# devboard-rf.net
KiCad netlist of a schematic drawn in EAGLE
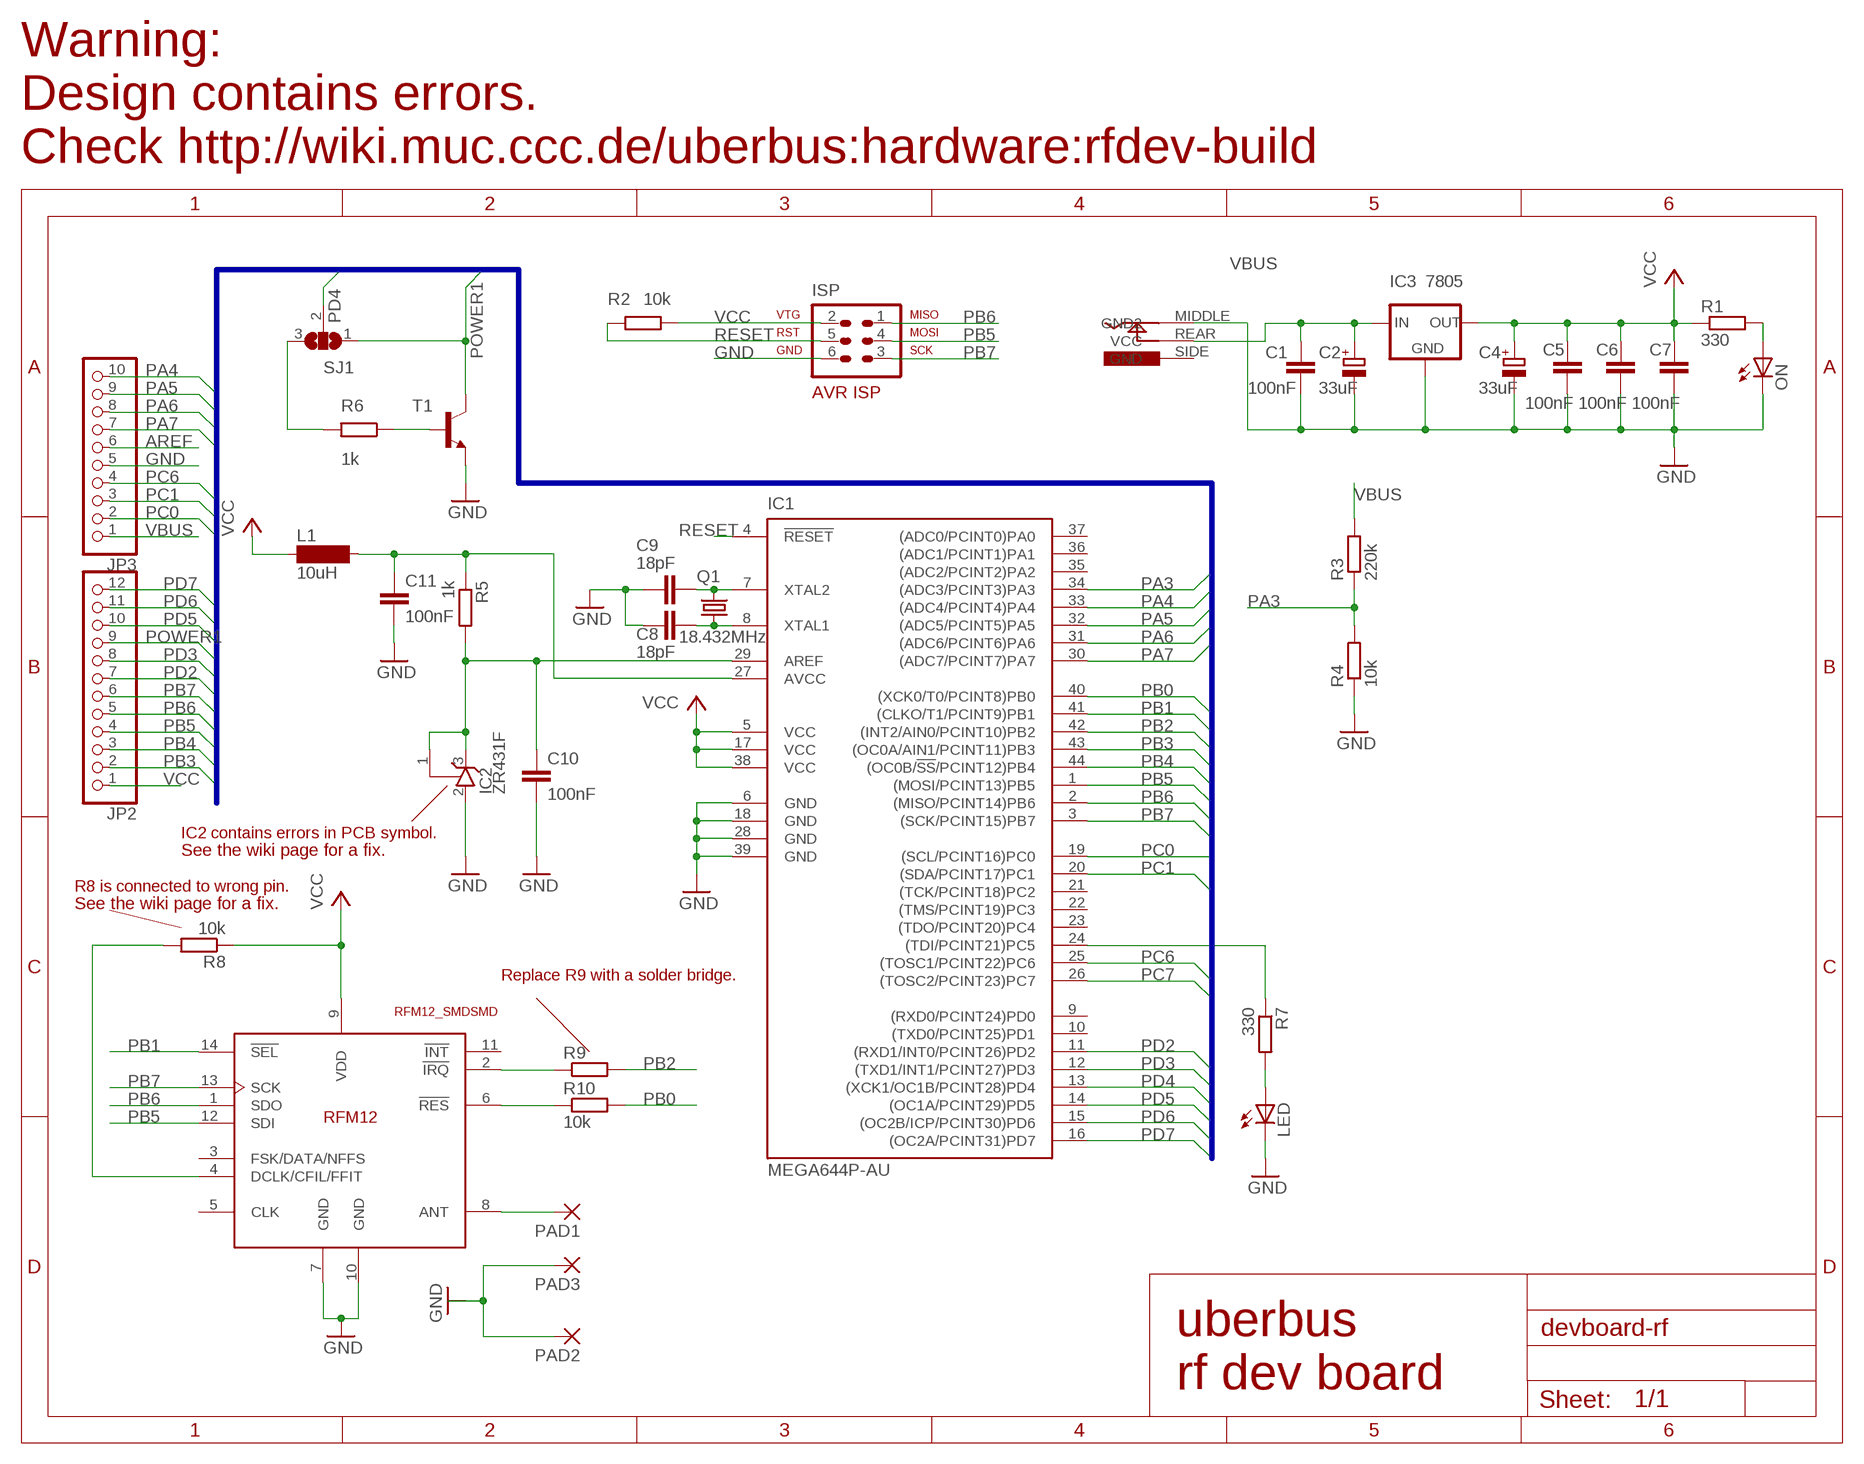
[diagram p0: schematic, sheet 1]

(export (version "E")
  (design (tool "Eeschema 10.0.6"))
  (components
    (comp (ref "C1")
      (value "100nF")
      (footprint "eagle-import:C0805K")
      (libsource (lib "eagle-import") (part "C-EUC0805K"))
    )
    (comp (ref "C2")
      (value "33uF")
      (footprint "eagle-import:E2,5-5")
      (libsource (lib "eagle-import") (part "CPOL-EUE2.5-5"))
    )
    (comp (ref "C4")
      (value "33uF")
      (footprint "eagle-import:E2,5-5")
      (libsource (lib "eagle-import") (part "CPOL-EUE2.5-5"))
    )
    (comp (ref "C5")
      (value "100nF")
      (footprint "eagle-import:C0805K")
      (libsource (lib "eagle-import") (part "C-EUC0805K"))
    )
    (comp (ref "C6")
      (value "100nF")
      (footprint "eagle-import:C0805K")
      (libsource (lib "eagle-import") (part "C-EUC0805K"))
    )
    (comp (ref "C7")
      (value "100nF")
      (footprint "eagle-import:C0805K")
      (libsource (lib "eagle-import") (part "C-EUC0805K"))
    )
    (comp (ref "C8")
      (value "18pF")
      (footprint "eagle-import:C0805K")
      (libsource (lib "eagle-import") (part "C-EUC0805K"))
    )
    (comp (ref "C9")
      (value "18pF")
      (footprint "eagle-import:C0805K")
      (libsource (lib "eagle-import") (part "C-EUC0805K"))
    )
    (comp (ref "C10")
      (value "100nF")
      (footprint "eagle-import:C0805K")
      (libsource (lib "eagle-import") (part "C-EUC0805K"))
    )
    (comp (ref "C11")
      (value "100nF")
      (footprint "eagle-import:C0805K")
      (libsource (lib "eagle-import") (part "C-EUC0805K"))
    )
    (comp (ref "IC1")
      (value "MEGA644P-AU")
      (footprint "eagle-import:TQFP44")
      (libsource (lib "eagle-import") (part "MEGA164P/324P/644P-AU"))
    )
    (comp (ref "IC2")
      (value "ZR431F")
      (footprint "eagle-import:SOT32")
      (libsource (lib "eagle-import") (part "ZR431F"))
    )
    (comp (ref "IC3")
      (value "7805")
      (footprint "eagle-import:78XXS")
      (libsource (lib "eagle-import") (part "78XXS"))
    )
    (comp (ref "ISP")
      (value "AVR-ISP-6")
      (footprint "eagle-import:AVR-ISP-6")
      (libsource (lib "eagle-import") (part "AVR-ISP-6"))
    )
    (comp (ref "JP2")
      (value "PINHD-1X12")
      (footprint "eagle-import:1X12")
      (libsource (lib "eagle-import") (part "PINHD-1X12"))
    )
    (comp (ref "JP3")
      (value "PINHD-1X10")
      (footprint "eagle-import:1X10")
      (libsource (lib "eagle-import") (part "PINHD-1X10"))
    )
    (comp (ref "L1")
      (value "10uH")
      (footprint "eagle-import:SM-1206")
      (libsource (lib "eagle-import") (part "SM-1206"))
    )
    (comp (ref "LED")
      (value "LEDCHIPLED_0805")
      (footprint "eagle-import:CHIPLED_0805")
      (libsource (lib "eagle-import") (part "LEDCHIPLED_0805"))
    )
    (comp (ref "ON")
      (value "LEDCHIPLED_0805")
      (footprint "eagle-import:CHIPLED_0805")
      (libsource (lib "eagle-import") (part "LEDCHIPLED_0805"))
    )
    (comp (ref "PAD1")
      (value "SMD2")
      (footprint "eagle-import:SMD1,27-2,54")
      (libsource (lib "eagle-import") (part "SMD2"))
    )
    (comp (ref "PAD2")
      (value "SMD2")
      (footprint "eagle-import:SMD1,27-2,54")
      (libsource (lib "eagle-import") (part "SMD2"))
    )
    (comp (ref "PAD3")
      (value "SMD2")
      (footprint "eagle-import:SMD1,27-2,54")
      (libsource (lib "eagle-import") (part "SMD2"))
    )
    (comp (ref "Q1")
      (value "18.432MHz")
      (footprint "eagle-import:HC49UP")
      (libsource (lib "eagle-import") (part "CRYSTALHC49UP"))
    )
    (comp (ref "R1")
      (value "330")
      (footprint "eagle-import:R0805")
      (libsource (lib "eagle-import") (part "R-EU_R0805"))
    )
    (comp (ref "R2")
      (value "10k")
      (footprint "eagle-import:R0805")
      (libsource (lib "eagle-import") (part "R-EU_R0805"))
    )
    (comp (ref "R3")
      (value "220k")
      (footprint "eagle-import:R0805")
      (libsource (lib "eagle-import") (part "R-EU_R0805"))
    )
    (comp (ref "R4")
      (value "10k")
      (footprint "eagle-import:R0805")
      (libsource (lib "eagle-import") (part "R-EU_R0805"))
    )
    (comp (ref "R5")
      (value "1k")
      (footprint "eagle-import:R0805")
      (libsource (lib "eagle-import") (part "R-EU_R0805"))
    )
    (comp (ref "R6")
      (value "1k")
      (footprint "eagle-import:R0805")
      (libsource (lib "eagle-import") (part "R-EU_R0805"))
    )
    (comp (ref "R7")
      (value "330")
      (footprint "eagle-import:R0805")
      (libsource (lib "eagle-import") (part "R-EU_R0805"))
    )
    (comp (ref "R8")
      (value "10k")
      (footprint "eagle-import:R0805")
      (libsource (lib "eagle-import") (part "R-EU_R0805"))
    )
    (comp (ref "R9")
      (value "0")
      (footprint "eagle-import:R0805")
      (libsource (lib "eagle-import") (part "R-EU_R0805"))
    )
    (comp (ref "R10")
      (value "10k")
      (footprint "eagle-import:R0805")
      (libsource (lib "eagle-import") (part "R-EU_R0805"))
    )
    (comp (ref "SJ1")
      (value "SJ2W")
      (footprint "eagle-import:SJ_2")
      (libsource (lib "eagle-import") (part "SJ2W"))
    )
    (comp (ref "T1")
      (value "MMBT2222ALT1-NPN-SOT23-BEC")
      (footprint "eagle-import:SOT23-BEC")
      (libsource (lib "eagle-import") (part "-NPN-SOT23-BECMMBT2222ALT1"))
    )
    (comp (ref "U$1")
      (value "RFM12_SMDSMD")
      (footprint "eagle-import:RFM12")
      (libsource (lib "eagle-import") (part "RFM12_SMDSMD"))
    )
    (comp (ref "U$2")
      (value "JACK-2.1MM")
      (footprint "eagle-import:JACK-2.1MM")
      (libsource (lib "eagle-import") (part "JACK-2.1MM"))
    )
  )
  (nets
    (net (code "1") (name "/AREF") (class "Default")
      (node (ref "C10") (pin "1") (pinfunction "1_1") (pintype "passive"))
      (node (ref "IC1") (pin "29") (pinfunction "AREF_29") (pintype "power_in"))
      (node (ref "IC2") (pin "1") (pinfunction "R_1") (pintype "passive"))
      (node (ref "IC2") (pin "3") (pinfunction "C_3") (pintype "passive"))
      (node (ref "JP3") (pin "6") (pinfunction "6_6") (pintype "passive"))
      (node (ref "R5") (pin "2") (pinfunction "2_2") (pintype "passive"))
    )
    (net (code "2") (name "/PA3") (class "Default")
      (node (ref "IC1") (pin "34") (pinfunction "(ADC3/PCINT3)PA3_34") (pintype "bidirectional"))
      (node (ref "R3") (pin "1") (pinfunction "1_1") (pintype "passive"))
      (node (ref "R4") (pin "2") (pinfunction "2_2") (pintype "passive"))
    )
    (net (code "3") (name "/PA4") (class "Default")
      (node (ref "IC1") (pin "33") (pinfunction "(ADC4/PCINT4)PA4_33") (pintype "bidirectional"))
      (node (ref "JP3") (pin "10") (pinfunction "10_10") (pintype "passive"))
    )
    (net (code "4") (name "/PA5") (class "Default")
      (node (ref "IC1") (pin "32") (pinfunction "(ADC5/PCINT5)PA5_32") (pintype "bidirectional"))
      (node (ref "JP3") (pin "9") (pinfunction "9_9") (pintype "passive"))
    )
    (net (code "5") (name "/PA6") (class "Default")
      (node (ref "IC1") (pin "31") (pinfunction "(ADC6/PCINT6)PA6_31") (pintype "bidirectional"))
      (node (ref "JP3") (pin "8") (pinfunction "8_8") (pintype "passive"))
    )
    (net (code "6") (name "/PA7") (class "Default")
      (node (ref "IC1") (pin "30") (pinfunction "(ADC7/PCINT7)PA7_30") (pintype "bidirectional"))
      (node (ref "JP3") (pin "7") (pinfunction "7_7") (pintype "passive"))
    )
    (net (code "7") (name "/PB0") (class "Default")
      (node (ref "IC1") (pin "40") (pinfunction "(XCK0/T0/PCINT8)PB0_40") (pintype "bidirectional"))
      (node (ref "R10") (pin "2") (pinfunction "2_2") (pintype "passive"))
    )
    (net (code "8") (name "/PB1") (class "Default")
      (node (ref "IC1") (pin "41") (pinfunction "(CLKO/T1/PCINT9)PB1_41") (pintype "bidirectional"))
      (node (ref "U$1") (pin "14") (pinfunction "~{SEL}_14") (pintype "input"))
    )
    (net (code "9") (name "/PB2") (class "Default")
      (node (ref "IC1") (pin "42") (pinfunction "(INT2/AIN0/PCINT10)PB2_42") (pintype "bidirectional"))
      (node (ref "R9") (pin "2") (pinfunction "2_2") (pintype "passive"))
    )
    (net (code "10") (name "/PB3") (class "Default")
      (node (ref "IC1") (pin "43") (pinfunction "(OC0A/AIN1/PCINT11)PB3_43") (pintype "bidirectional"))
      (node (ref "JP2") (pin "2") (pinfunction "2_2") (pintype "passive"))
    )
    (net (code "11") (name "/PB4") (class "Default")
      (node (ref "IC1") (pin "44") (pinfunction "(OC0B/~{SS}/PCINT12)PB4_44") (pintype "bidirectional"))
      (node (ref "JP2") (pin "3") (pinfunction "3_3") (pintype "passive"))
    )
    (net (code "12") (name "/PB5") (class "Default")
      (node (ref "IC1") (pin "1") (pinfunction "(MOSI/PCINT13)PB5_1") (pintype "bidirectional"))
      (node (ref "ISP") (pin "4") (pinfunction "4_4") (pintype "passive"))
      (node (ref "JP2") (pin "4") (pinfunction "4_4") (pintype "passive"))
      (node (ref "U$1") (pin "12") (pinfunction "SDI_12") (pintype "input"))
    )
    (net (code "13") (name "/PB6") (class "Default")
      (node (ref "IC1") (pin "2") (pinfunction "(MISO/PCINT14)PB6_2") (pintype "bidirectional"))
      (node (ref "ISP") (pin "1") (pinfunction "1_1") (pintype "passive"))
      (node (ref "JP2") (pin "5") (pinfunction "5_5") (pintype "passive"))
      (node (ref "U$1") (pin "1") (pinfunction "SDO_1") (pintype "output"))
    )
    (net (code "14") (name "/PB7") (class "Default")
      (node (ref "IC1") (pin "3") (pinfunction "(SCK/PCINT15)PB7_3") (pintype "bidirectional"))
      (node (ref "ISP") (pin "3") (pinfunction "3_3") (pintype "passive"))
      (node (ref "JP2") (pin "6") (pinfunction "6_6") (pintype "passive"))
      (node (ref "U$1") (pin "13") (pinfunction "SCK_13") (pintype "input"))
    )
    (net (code "15") (name "/PC0") (class "Default")
      (node (ref "IC1") (pin "19") (pinfunction "(SCL/PCINT16)PC0_19") (pintype "bidirectional"))
      (node (ref "JP3") (pin "2") (pinfunction "2_2") (pintype "passive"))
    )
    (net (code "16") (name "/PC1") (class "Default")
      (node (ref "IC1") (pin "20") (pinfunction "(SDA/PCINT17)PC1_20") (pintype "bidirectional"))
      (node (ref "JP3") (pin "3") (pinfunction "3_3") (pintype "passive"))
    )
    (net (code "17") (name "/PC6") (class "Default")
      (node (ref "IC1") (pin "25") (pinfunction "(TOSC1/PCINT22)PC6_25") (pintype "bidirectional"))
      (node (ref "JP3") (pin "4") (pinfunction "4_4") (pintype "passive"))
    )
    (net (code "18") (name "/PC7") (class "Default")
      (node (ref "IC1") (pin "26") (pinfunction "(TOSC2/PCINT23)PC7_26") (pintype "bidirectional"))
    )
    (net (code "19") (name "/PD2") (class "Default")
      (node (ref "IC1") (pin "11") (pinfunction "(RXD1/INT0/PCINT26)PD2_11") (pintype "bidirectional"))
      (node (ref "JP2") (pin "7") (pinfunction "7_7") (pintype "passive"))
    )
    (net (code "20") (name "/PD3") (class "Default")
      (node (ref "IC1") (pin "12") (pinfunction "(TXD1/INT1/PCINT27)PD3_12") (pintype "bidirectional"))
      (node (ref "JP2") (pin "8") (pinfunction "8_8") (pintype "passive"))
    )
    (net (code "21") (name "/PD4") (class "Default")
      (node (ref "IC1") (pin "13") (pinfunction "(XCK1/OC1B/PCINT28)PD4_13") (pintype "bidirectional"))
      (node (ref "SJ1") (pin "2") (pinfunction "2_2") (pintype "passive"))
    )
    (net (code "22") (name "/PD5") (class "Default")
      (node (ref "IC1") (pin "14") (pinfunction "(OC1A/PCINT29)PD5_14") (pintype "bidirectional"))
      (node (ref "JP2") (pin "10") (pinfunction "10_10") (pintype "passive"))
    )
    (net (code "23") (name "/PD6") (class "Default")
      (node (ref "IC1") (pin "15") (pinfunction "(OC2B/ICP/PCINT30)PD6_15") (pintype "bidirectional"))
      (node (ref "JP2") (pin "11") (pinfunction "11_11") (pintype "passive"))
    )
    (net (code "24") (name "/PD7") (class "Default")
      (node (ref "IC1") (pin "16") (pinfunction "(OC2A/PCINT31)PD7_16") (pintype "bidirectional"))
      (node (ref "JP2") (pin "12") (pinfunction "12_12") (pintype "passive"))
    )
    (net (code "25") (name "/POWER1") (class "Default")
      (node (ref "JP2") (pin "9") (pinfunction "9_9") (pintype "passive"))
      (node (ref "SJ1") (pin "1") (pinfunction "1_1") (pintype "passive"))
      (node (ref "T1") (pin "C") (pinfunction "C_C") (pintype "passive"))
    )
    (net (code "26") (name "/RESET") (class "Default")
      (node (ref "IC1") (pin "4") (pinfunction "~{RESET}_4") (pintype "input"))
      (node (ref "ISP") (pin "5") (pinfunction "5_5") (pintype "passive"))
      (node (ref "R2") (pin "1") (pinfunction "1_1") (pintype "passive"))
    )
    (net (code "27") (name "/VBUS") (class "Default")
      (node (ref "C1") (pin "2") (pinfunction "2_2") (pintype "passive"))
      (node (ref "C2") (pin "+") (pinfunction "+_+") (pintype "passive"))
      (node (ref "IC3") (pin "IN") (pinfunction "IN_IN") (pintype "input"))
      (node (ref "JP3") (pin "1") (pinfunction "1_1") (pintype "passive"))
      (node (ref "R3") (pin "2") (pinfunction "2_2") (pintype "passive"))
      (node (ref "U$2") (pin "REAR") (pinfunction "VCC_REAR") (pintype "bidirectional"))
    )
    (net (code "28") (name "GND") (class "Default")
      (node (ref "C1") (pin "1") (pinfunction "1_1") (pintype "passive"))
      (node (ref "C10") (pin "2") (pinfunction "2_2") (pintype "passive"))
      (node (ref "C11") (pin "2") (pinfunction "2_2") (pintype "passive"))
      (node (ref "C2") (pin "-") (pinfunction "-_-") (pintype "passive"))
      (node (ref "C4") (pin "-") (pinfunction "-_-") (pintype "passive"))
      (node (ref "C5") (pin "1") (pinfunction "1_1") (pintype "passive"))
      (node (ref "C6") (pin "1") (pinfunction "1_1") (pintype "passive"))
      (node (ref "C7") (pin "1") (pinfunction "1_1") (pintype "passive"))
      (node (ref "C8") (pin "2") (pinfunction "2_2") (pintype "passive"))
      (node (ref "C9") (pin "2") (pinfunction "2_2") (pintype "passive"))
      (node (ref "IC1") (pin "18") (pinfunction "GND_18") (pintype "power_in"))
      (node (ref "IC1") (pin "28") (pinfunction "GND_28") (pintype "power_in"))
      (node (ref "IC1") (pin "39") (pinfunction "GND_39") (pintype "power_in"))
      (node (ref "IC1") (pin "6") (pinfunction "GND_6") (pintype "power_in"))
      (node (ref "IC2") (pin "2") (pinfunction "A_2") (pintype "passive"))
      (node (ref "IC3") (pin "GND") (pinfunction "GND_GND") (pintype "input"))
      (node (ref "ISP") (pin "6") (pinfunction "6_6") (pintype "passive"))
      (node (ref "JP3") (pin "5") (pinfunction "5_5") (pintype "passive"))
      (node (ref "LED") (pin "C") (pinfunction "C_C") (pintype "passive"))
      (node (ref "ON") (pin "C") (pinfunction "C_C") (pintype "passive"))
      (node (ref "R4") (pin "1") (pinfunction "1_1") (pintype "passive"))
      (node (ref "T1") (pin "E") (pinfunction "E_E") (pintype "passive"))
      (node (ref "U$1") (pin "10") (pinfunction "GND_10") (pintype "passive"))
      (node (ref "U$1") (pin "7") (pinfunction "GND_7") (pintype "passive"))
      (node (ref "U$2") (pin "MIDDLE") (pinfunction "GND2_MIDDLE") (pintype "bidirectional"))
    )
    (net (code "29") (name "Net-(IC1-(TDI{slash}PCINT21)PC5)") (class "Default")
      (node (ref "IC1") (pin "24") (pinfunction "(TDI/PCINT21)PC5_24") (pintype "bidirectional"))
      (node (ref "R7") (pin "1") (pinfunction "1_1") (pintype "passive"))
    )
    (net (code "30") (name "Net-(IC1-AVCC)") (class "Default")
      (node (ref "C11") (pin "1") (pinfunction "1_1") (pintype "passive"))
      (node (ref "IC1") (pin "27") (pinfunction "AVCC_27") (pintype "power_in"))
      (node (ref "L1") (pin "2") (pinfunction "2_2") (pintype "passive"))
      (node (ref "R5") (pin "1") (pinfunction "1_1") (pintype "passive"))
    )
    (net (code "31") (name "Net-(IC1-XTAL1)") (class "Default")
      (node (ref "C8") (pin "1") (pinfunction "1_1") (pintype "passive"))
      (node (ref "IC1") (pin "8") (pinfunction "XTAL1_8") (pintype "input"))
      (node (ref "Q1") (pin "1") (pinfunction "1_1") (pintype "passive"))
    )
    (net (code "32") (name "Net-(IC1-XTAL2)") (class "Default")
      (node (ref "C9") (pin "1") (pinfunction "1_1") (pintype "passive"))
      (node (ref "IC1") (pin "7") (pinfunction "XTAL2_7") (pintype "output"))
      (node (ref "Q1") (pin "2") (pinfunction "2_2") (pintype "passive"))
    )
    (net (code "33") (name "Net-(LED-PadA)") (class "Default")
      (node (ref "LED") (pin "A") (pinfunction "A_A") (pintype "passive"))
      (node (ref "R7") (pin "2") (pinfunction "2_2") (pintype "passive"))
    )
    (net (code "34") (name "Net-(ON-PadA)") (class "Default")
      (node (ref "ON") (pin "A") (pinfunction "A_A") (pintype "passive"))
      (node (ref "R1") (pin "2") (pinfunction "2_2") (pintype "passive"))
    )
    (net (code "35") (name "Net-(PAD1-P)") (class "Default")
      (node (ref "PAD1") (pin "1") (pinfunction "P_1") (pintype "passive"))
      (node (ref "U$1") (pin "8") (pinfunction "ANT_8") (pintype "bidirectional"))
    )
    (net (code "36") (name "Net-(PAD2-P)") (class "Default")
      (node (ref "PAD2") (pin "1") (pinfunction "P_1") (pintype "passive"))
      (node (ref "PAD3") (pin "1") (pinfunction "P_1") (pintype "passive"))
    )
    (net (code "37") (name "Net-(R6-Pad1)") (class "Default")
      (node (ref "R6") (pin "1") (pinfunction "1_1") (pintype "passive"))
      (node (ref "T1") (pin "B") (pinfunction "B_B") (pintype "passive"))
    )
    (net (code "38") (name "Net-(R6-Pad2)") (class "Default")
      (node (ref "R6") (pin "2") (pinfunction "2_2") (pintype "passive"))
      (node (ref "SJ1") (pin "3") (pinfunction "3_3") (pintype "passive"))
    )
    (net (code "39") (name "Net-(U$1-DCLK{slash}CFIL{slash}FFIT)") (class "Default")
      (node (ref "R8") (pin "2") (pinfunction "2_2") (pintype "passive"))
      (node (ref "U$1") (pin "4") (pinfunction "DCLK/CFIL/FFIT_4") (pintype "bidirectional"))
    )
    (net (code "40") (name "Net-(U$1-~{IRQ})") (class "Default")
      (node (ref "R9") (pin "1") (pinfunction "1_1") (pintype "passive"))
      (node (ref "U$1") (pin "2") (pinfunction "~{IRQ}_2") (pintype "output"))
    )
    (net (code "41") (name "Net-(U$1-~{RES})") (class "Default")
      (node (ref "R10") (pin "1") (pinfunction "1_1") (pintype "passive"))
      (node (ref "U$1") (pin "6") (pinfunction "~{RES}_6") (pintype "bidirectional"))
    )
    (net (code "42") (name "VCC") (class "Default")
      (node (ref "C4") (pin "+") (pinfunction "+_+") (pintype "passive"))
      (node (ref "C5") (pin "2") (pinfunction "2_2") (pintype "passive"))
      (node (ref "C6") (pin "2") (pinfunction "2_2") (pintype "passive"))
      (node (ref "C7") (pin "2") (pinfunction "2_2") (pintype "passive"))
      (node (ref "IC1") (pin "17") (pinfunction "VCC_17") (pintype "power_in"))
      (node (ref "IC1") (pin "38") (pinfunction "VCC_38") (pintype "power_in"))
      (node (ref "IC1") (pin "5") (pinfunction "VCC_5") (pintype "power_in"))
      (node (ref "IC3") (pin "OUT") (pinfunction "OUT_OUT") (pintype "passive"))
      (node (ref "ISP") (pin "2") (pinfunction "2_2") (pintype "passive"))
      (node (ref "JP2") (pin "1") (pinfunction "1_1") (pintype "passive"))
      (node (ref "L1") (pin "1") (pinfunction "1_1") (pintype "passive"))
      (node (ref "R1") (pin "1") (pinfunction "1_1") (pintype "passive"))
      (node (ref "R2") (pin "2") (pinfunction "2_2") (pintype "passive"))
      (node (ref "R8") (pin "1") (pinfunction "1_1") (pintype "passive"))
      (node (ref "U$1") (pin "9") (pinfunction "VDD_9") (pintype "power_in"))
    )
    (net (code "43") (name "unconnected-(IC1-(ADC0{slash}PCINT0)PA0-Pad37)") (class "Default")
      (node (ref "IC1") (pin "37") (pinfunction "(ADC0/PCINT0)PA0_37") (pintype "bidirectional"))
    )
    (net (code "44") (name "unconnected-(IC1-(ADC1{slash}PCINT1)PA1-Pad36)") (class "Default")
      (node (ref "IC1") (pin "36") (pinfunction "(ADC1/PCINT1)PA1_36") (pintype "bidirectional"))
    )
    (net (code "45") (name "unconnected-(IC1-(ADC2{slash}PCINT2)PA2-Pad35)") (class "Default")
      (node (ref "IC1") (pin "35") (pinfunction "(ADC2/PCINT2)PA2_35") (pintype "bidirectional"))
    )
    (net (code "46") (name "unconnected-(IC1-(RXD0{slash}PCINT24)PD0-Pad9)") (class "Default")
      (node (ref "IC1") (pin "9") (pinfunction "(RXD0/PCINT24)PD0_9") (pintype "bidirectional"))
    )
    (net (code "47") (name "unconnected-(IC1-(TCK{slash}PCINT18)PC2-Pad21)") (class "Default")
      (node (ref "IC1") (pin "21") (pinfunction "(TCK/PCINT18)PC2_21") (pintype "bidirectional"))
    )
    (net (code "48") (name "unconnected-(IC1-(TDO{slash}PCINT20)PC4-Pad23)") (class "Default")
      (node (ref "IC1") (pin "23") (pinfunction "(TDO/PCINT20)PC4_23") (pintype "bidirectional"))
    )
    (net (code "49") (name "unconnected-(IC1-(TMS{slash}PCINT19)PC3-Pad22)") (class "Default")
      (node (ref "IC1") (pin "22") (pinfunction "(TMS/PCINT19)PC3_22") (pintype "bidirectional"))
    )
    (net (code "50") (name "unconnected-(IC1-(TXD0{slash}PCINT25)PD1-Pad10)") (class "Default")
      (node (ref "IC1") (pin "10") (pinfunction "(TXD0/PCINT25)PD1_10") (pintype "bidirectional"))
    )
    (net (code "51") (name "unconnected-(U$1-CLK-Pad5)") (class "Default")
      (node (ref "U$1") (pin "5") (pinfunction "CLK_5") (pintype "output"))
    )
    (net (code "52") (name "unconnected-(U$1-FSK{slash}DATA{slash}NFFS-Pad3)") (class "Default")
      (node (ref "U$1") (pin "3") (pinfunction "FSK/DATA/NFFS_3") (pintype "bidirectional"))
    )
    (net (code "53") (name "unconnected-(U$1-~{INT}-Pad11)") (class "Default")
      (node (ref "U$1") (pin "11") (pinfunction "~{INT}_11") (pintype "bidirectional"))
    )
    (net (code "54") (name "unconnected-(U$2-GND-PadSIDE)") (class "Default")
      (node (ref "U$2") (pin "SIDE") (pinfunction "GND_SIDE") (pintype "bidirectional"))
    )
  )
)
